# Mind-Synchronizing-Generator-PinHdrPot-C.net
KiCad netlist of a schematic drawn in EAGLE
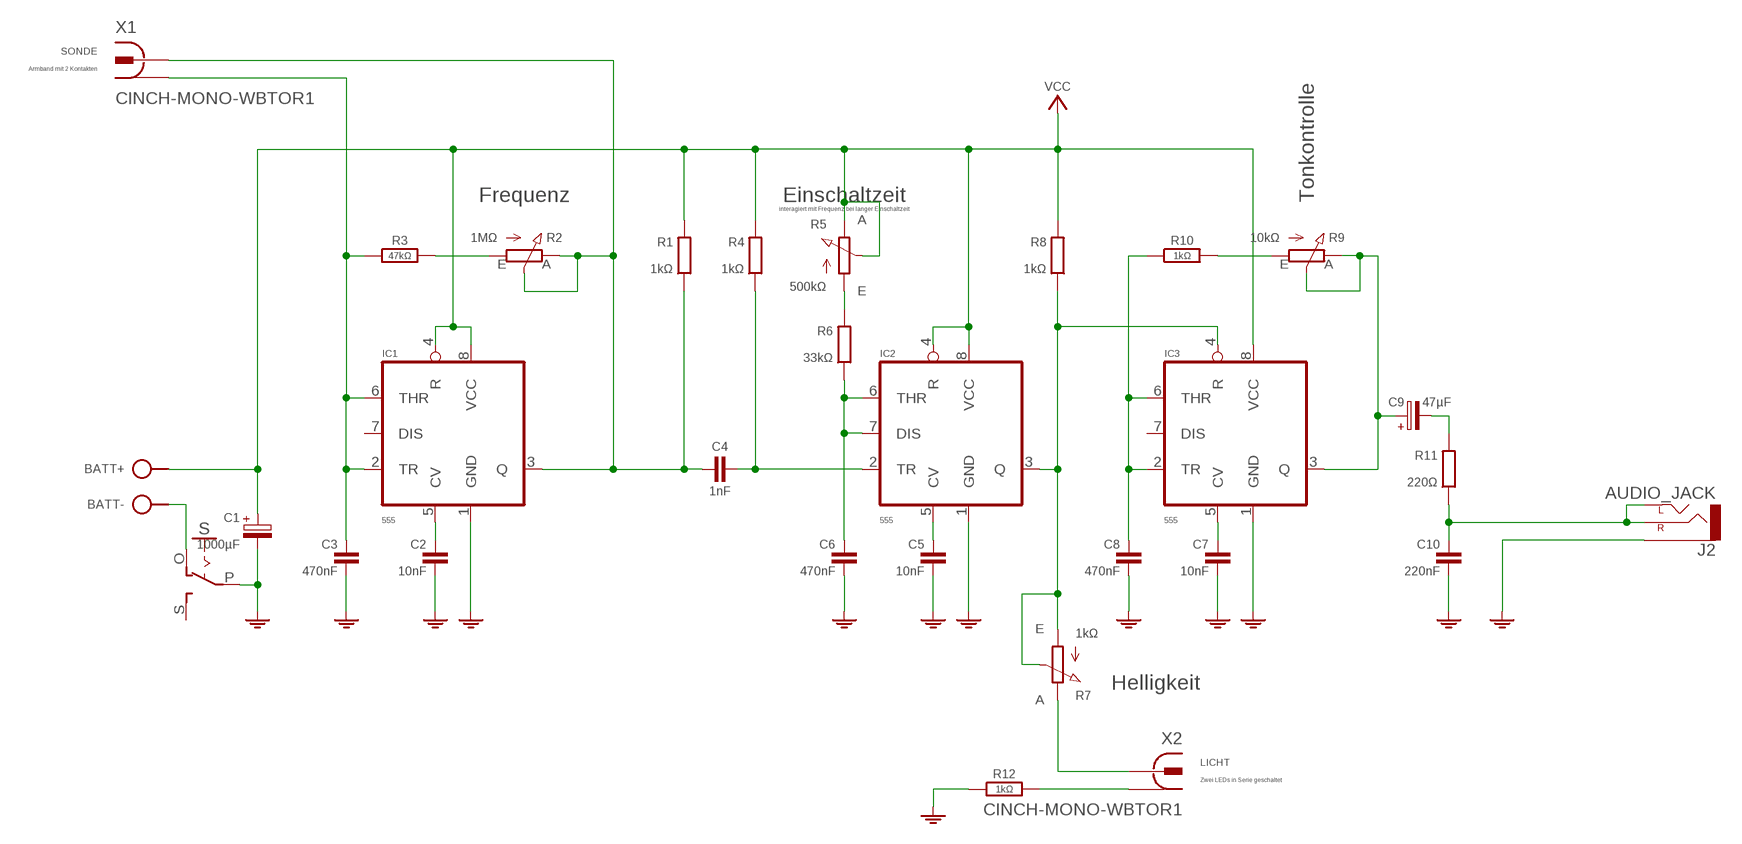
[diagram p0: schematic, sheet 1]

(export (version "E")
  (design (tool "Eeschema 10.0.6"))
  (components
    (comp (ref "BATT")
      (value "SPAD+--+")
      (footprint "eagle-import:SPAD-+")
      (libsource (lib "eagle-import") (part "SPAD+--+"))
    )
    (comp (ref "C1")
      (value "1000µF")
      (footprint "eagle-import:E2,5-6")
      (libsource (lib "eagle-import") (part "CPOLE2.5-6"))
    )
    (comp (ref "C2")
      (value "10nF")
      (footprint "eagle-import:C050-020X044")
      (libsource (lib "eagle-import") (part "C050-020X044"))
    )
    (comp (ref "C3")
      (value "470nF")
      (footprint "eagle-import:C050-040X075")
      (libsource (lib "eagle-import") (part "C050-040X075"))
    )
    (comp (ref "C4")
      (value "1nF")
      (footprint "eagle-import:C050-020X044")
      (libsource (lib "eagle-import") (part "C-H050-020X044"))
    )
    (comp (ref "C5")
      (value "10nF")
      (footprint "eagle-import:C050-020X044_V")
      (libsource (lib "eagle-import") (part "C050-020X044/V"))
    )
    (comp (ref "C6")
      (value "470nF")
      (footprint "eagle-import:C050-040X075")
      (libsource (lib "eagle-import") (part "C050-040X075"))
    )
    (comp (ref "C7")
      (value "10nF")
      (footprint "eagle-import:C050-020X044_V")
      (libsource (lib "eagle-import") (part "C050-020X044/V"))
    )
    (comp (ref "C8")
      (value "470nF")
      (footprint "eagle-import:C050-040X075")
      (libsource (lib "eagle-import") (part "C050-040X075"))
    )
    (comp (ref "C9")
      (value "47µF")
      (footprint "eagle-import:E2,5-4")
      (libsource (lib "eagle-import") (part "CPOL-HE2,5-4"))
    )
    (comp (ref "C10")
      (value "220nF")
      (footprint "eagle-import:C050-025X060")
      (libsource (lib "eagle-import") (part "C025-025X060"))
    )
    (comp (ref "IC1")
      (value "555")
      (footprint "eagle-import:555-DIL")
      (libsource (lib "eagle-import") (part "555_ALT2-LBL"))
    )
    (comp (ref "IC2")
      (value "555")
      (footprint "eagle-import:555-DIL")
      (libsource (lib "eagle-import") (part "555_ALT2-LBL"))
    )
    (comp (ref "IC3")
      (value "555")
      (footprint "eagle-import:555-DIL")
      (libsource (lib "eagle-import") (part "555_ALT2-LBL"))
    )
    (comp (ref "J2")
      (value "AUDIO_JACK")
      (footprint "eagle-import:AUDIO-JACK")
      (libsource (lib "eagle-import") (part "AUDIO_JACK"))
    )
    (comp (ref "R1")
      (value "1kΩ")
      (footprint "eagle-import:0204_10")
      (libsource (lib "eagle-import") (part "R0204/10"))
    )
    (comp (ref "R2")
      (value "1MΩ")
      (footprint "eagle-import:CONN-3P")
      (libsource (lib "eagle-import") (part "POT-H-3P"))
    )
    (comp (ref "R3")
      (value "47kΩ")
      (footprint "eagle-import:0204_10")
      (libsource (lib "eagle-import") (part "R-H0204/10"))
    )
    (comp (ref "R4")
      (value "1kΩ")
      (footprint "eagle-import:0204_10-V")
      (libsource (lib "eagle-import") (part "R0204/10-V"))
    )
    (comp (ref "R5")
      (value "500kΩ")
      (footprint "eagle-import:CONN-3P")
      (libsource (lib "eagle-import") (part "POT-3P"))
    )
    (comp (ref "R6")
      (value "33kΩ")
      (footprint "eagle-import:0204_10")
      (libsource (lib "eagle-import") (part "R0204/10"))
    )
    (comp (ref "R7")
      (value "1kΩ")
      (footprint "eagle-import:CONN-3P")
      (libsource (lib "eagle-import") (part "POT-3P"))
    )
    (comp (ref "R8")
      (value "1kΩ")
      (footprint "eagle-import:0204_10-V")
      (libsource (lib "eagle-import") (part "R0204/10-V"))
    )
    (comp (ref "R9")
      (value "10kΩ")
      (footprint "eagle-import:CONN-3P")
      (libsource (lib "eagle-import") (part "POT-H-3P"))
    )
    (comp (ref "R10")
      (value "1kΩ")
      (footprint "eagle-import:0204_10")
      (libsource (lib "eagle-import") (part "R-H0204/10"))
    )
    (comp (ref "R11")
      (value "220Ω")
      (footprint "eagle-import:0204_10-V")
      (libsource (lib "eagle-import") (part "R0204/10-V"))
    )
    (comp (ref "R12")
      (value "1kΩ")
      (footprint "eagle-import:0204_10")
      (libsource (lib "eagle-import") (part "R-H0204/10"))
    )
    (comp (ref "S")
      (value "SL-SW-1P-2T-V2")
      (footprint "eagle-import:SLSW-1P2T-V2")
      (libsource (lib "eagle-import") (part "SL-SW-1P-2T-V2"))
    )
    (comp (ref "X1")
      (value "CINCH-MONO-WBTOR1")
      (footprint "eagle-import:WBTOR1")
      (libsource (lib "eagle-import") (part "CINCH-MONO-WBTOR1"))
    )
    (comp (ref "X2")
      (value "CINCH-MONO-WBTOR1")
      (footprint "eagle-import:WBTOR1")
      (libsource (lib "eagle-import") (part "CINCH-MONO-WBTOR1"))
    )
  )
  (nets
    (net (code "1") (name "GND") (class "Default")
      (node (ref "C1") (pin "-") (pinfunction "-_-") (pintype "passive"))
      (node (ref "C10") (pin "2") (pinfunction "2_2") (pintype "passive"))
      (node (ref "C2") (pin "2") (pinfunction "2_2") (pintype "passive"))
      (node (ref "C3") (pin "2") (pinfunction "2_2") (pintype "passive"))
      (node (ref "C5") (pin "2") (pinfunction "2_2") (pintype "passive"))
      (node (ref "C6") (pin "2") (pinfunction "2_2") (pintype "passive"))
      (node (ref "C7") (pin "2") (pinfunction "2_2") (pintype "passive"))
      (node (ref "C8") (pin "2") (pinfunction "2_2") (pintype "passive"))
      (node (ref "IC1") (pin "1") (pinfunction "GND_1") (pintype "power_in"))
      (node (ref "IC2") (pin "1") (pinfunction "GND_1") (pintype "power_in"))
      (node (ref "IC3") (pin "1") (pinfunction "GND_1") (pintype "power_in"))
      (node (ref "J2") (pin "SLEEVE") (pinfunction "SLEEVE_SLEEVE") (pintype "bidirectional"))
      (node (ref "R12") (pin "1") (pinfunction "1_1") (pintype "passive"))
      (node (ref "S") (pin "P") (pinfunction "P_P") (pintype "passive"))
    )
    (net (code "2") (name "Net-(BATTB-P$1)") (class "Default")
      (node (ref "BATT") (pin "1") (pinfunction "P$1_1") (pintype "passive"))
      (node (ref "S") (pin "O") (pinfunction "O_O") (pintype "passive"))
    )
    (net (code "3") (name "Net-(IC1-CV)") (class "Default")
      (node (ref "C2") (pin "1") (pinfunction "1_1") (pintype "passive"))
      (node (ref "IC1") (pin "5") (pinfunction "CV_5") (pintype "input"))
    )
    (net (code "4") (name "Net-(IC1-Q)") (class "Default")
      (node (ref "C4") (pin "1") (pinfunction "1_1") (pintype "passive"))
      (node (ref "IC1") (pin "3") (pinfunction "Q_3") (pintype "output"))
      (node (ref "R1") (pin "2") (pinfunction "1_2") (pintype "passive"))
      (node (ref "R2") (pin "2") (pinfunction "S_2") (pintype "passive"))
      (node (ref "R2") (pin "3") (pinfunction "E_3") (pintype "passive"))
      (node (ref "X1") (pin "U") (pinfunction "2_U") (pintype "passive"))
    )
    (net (code "5") (name "Net-(IC1-THR)") (class "Default")
      (node (ref "C3") (pin "1") (pinfunction "1_1") (pintype "passive"))
      (node (ref "IC1") (pin "2") (pinfunction "TR_2") (pintype "input"))
      (node (ref "IC1") (pin "6") (pinfunction "THR_6") (pintype "input"))
      (node (ref "R3") (pin "1") (pinfunction "1_1") (pintype "passive"))
      (node (ref "X1") (pin "T") (pinfunction "1_T") (pintype "passive"))
    )
    (net (code "6") (name "Net-(IC2-CV)") (class "Default")
      (node (ref "C5") (pin "1") (pinfunction "1_1") (pintype "passive"))
      (node (ref "IC2") (pin "5") (pinfunction "CV_5") (pintype "input"))
    )
    (net (code "7") (name "Net-(IC2-DIS)") (class "Default")
      (node (ref "C6") (pin "1") (pinfunction "1_1") (pintype "passive"))
      (node (ref "IC2") (pin "6") (pinfunction "THR_6") (pintype "input"))
      (node (ref "IC2") (pin "7") (pinfunction "DIS_7") (pintype "passive"))
      (node (ref "R6") (pin "2") (pinfunction "1_2") (pintype "passive"))
    )
    (net (code "8") (name "Net-(IC2-Q)") (class "Default")
      (node (ref "IC2") (pin "3") (pinfunction "Q_3") (pintype "output"))
      (node (ref "IC3") (pin "4") (pinfunction "R_4") (pintype "input"))
      (node (ref "R7") (pin "1") (pinfunction "A_1") (pintype "passive"))
      (node (ref "R7") (pin "2") (pinfunction "S_2") (pintype "passive"))
      (node (ref "R8") (pin "2") (pinfunction "1_2") (pintype "passive"))
    )
    (net (code "9") (name "Net-(IC2-TR)") (class "Default")
      (node (ref "C4") (pin "2") (pinfunction "2_2") (pintype "passive"))
      (node (ref "IC2") (pin "2") (pinfunction "TR_2") (pintype "input"))
      (node (ref "R4") (pin "2") (pinfunction "1_2") (pintype "passive"))
    )
    (net (code "10") (name "Net-(IC3-CV)") (class "Default")
      (node (ref "C7") (pin "1") (pinfunction "1_1") (pintype "passive"))
      (node (ref "IC3") (pin "5") (pinfunction "CV_5") (pintype "input"))
    )
    (net (code "11") (name "Net-(IC3-Q)") (class "Default")
      (node (ref "C9") (pin "+") (pinfunction "+_+") (pintype "passive"))
      (node (ref "IC3") (pin "3") (pinfunction "Q_3") (pintype "output"))
      (node (ref "R9") (pin "2") (pinfunction "S_2") (pintype "passive"))
      (node (ref "R9") (pin "3") (pinfunction "E_3") (pintype "passive"))
    )
    (net (code "12") (name "Net-(IC3-THR)") (class "Default")
      (node (ref "C8") (pin "1") (pinfunction "1_1") (pintype "passive"))
      (node (ref "IC3") (pin "2") (pinfunction "TR_2") (pintype "input"))
      (node (ref "IC3") (pin "6") (pinfunction "THR_6") (pintype "input"))
      (node (ref "R10") (pin "1") (pinfunction "1_1") (pintype "passive"))
    )
    (net (code "13") (name "Net-(J2-LEFT)") (class "Default")
      (node (ref "C10") (pin "1") (pinfunction "1_1") (pintype "passive"))
      (node (ref "J2") (pin "RING") (pinfunction "RIGHT_RING") (pintype "bidirectional"))
      (node (ref "J2") (pin "TIP") (pinfunction "LEFT_TIP") (pintype "bidirectional"))
      (node (ref "R11") (pin "2") (pinfunction "1_2") (pintype "passive"))
    )
    (net (code "14") (name "Net-(R2-A)") (class "Default")
      (node (ref "R2") (pin "1") (pinfunction "A_1") (pintype "passive"))
      (node (ref "R3") (pin "2") (pinfunction "2_2") (pintype "passive"))
    )
    (net (code "15") (name "Net-(R5-A)") (class "Default")
      (node (ref "R5") (pin "1") (pinfunction "A_1") (pintype "passive"))
      (node (ref "R6") (pin "1") (pinfunction "2_1") (pintype "passive"))
    )
    (net (code "16") (name "Net-(R7-E)") (class "Default")
      (node (ref "R7") (pin "3") (pinfunction "E_3") (pintype "passive"))
      (node (ref "X2") (pin "U") (pinfunction "2_U") (pintype "passive"))
    )
    (net (code "17") (name "Net-(R9-A)") (class "Default")
      (node (ref "R10") (pin "2") (pinfunction "2_2") (pintype "passive"))
      (node (ref "R9") (pin "1") (pinfunction "A_1") (pintype "passive"))
    )
    (net (code "18") (name "Net-(R11-2)") (class "Default")
      (node (ref "C9") (pin "-") (pinfunction "-_-") (pintype "passive"))
      (node (ref "R11") (pin "1") (pinfunction "2_1") (pintype "passive"))
    )
    (net (code "19") (name "Net-(X2-1)") (class "Default")
      (node (ref "R12") (pin "2") (pinfunction "2_2") (pintype "passive"))
      (node (ref "X2") (pin "T") (pinfunction "1_T") (pintype "passive"))
    )
    (net (code "20") (name "VCC") (class "Default")
      (node (ref "BATT") (pin "2") (pinfunction "P$1_2") (pintype "passive"))
      (node (ref "C1") (pin "+") (pinfunction "+_+") (pintype "passive"))
      (node (ref "IC1") (pin "4") (pinfunction "R_4") (pintype "input"))
      (node (ref "IC1") (pin "8") (pinfunction "VCC_8") (pintype "power_in"))
      (node (ref "IC2") (pin "4") (pinfunction "R_4") (pintype "input"))
      (node (ref "IC2") (pin "8") (pinfunction "VCC_8") (pintype "power_in"))
      (node (ref "IC3") (pin "8") (pinfunction "VCC_8") (pintype "power_in"))
      (node (ref "R1") (pin "1") (pinfunction "2_1") (pintype "passive"))
      (node (ref "R4") (pin "1") (pinfunction "2_1") (pintype "passive"))
      (node (ref "R5") (pin "2") (pinfunction "S_2") (pintype "passive"))
      (node (ref "R5") (pin "3") (pinfunction "E_3") (pintype "passive"))
      (node (ref "R8") (pin "1") (pinfunction "2_1") (pintype "passive"))
    )
    (net (code "21") (name "unconnected-(IC1-DIS-Pad7)") (class "Default")
      (node (ref "IC1") (pin "7") (pinfunction "DIS_7") (pintype "passive"))
    )
    (net (code "22") (name "unconnected-(IC3-DIS-Pad7)") (class "Default")
      (node (ref "IC3") (pin "7") (pinfunction "DIS_7") (pintype "passive"))
    )
    (net (code "23") (name "unconnected-(S-PadS)") (class "Default")
      (node (ref "S") (pin "S") (pinfunction "S_S") (pintype "passive"))
    )
  )
)
